# untitled.net
KiCad netlist of a schematic drawn in EAGLE
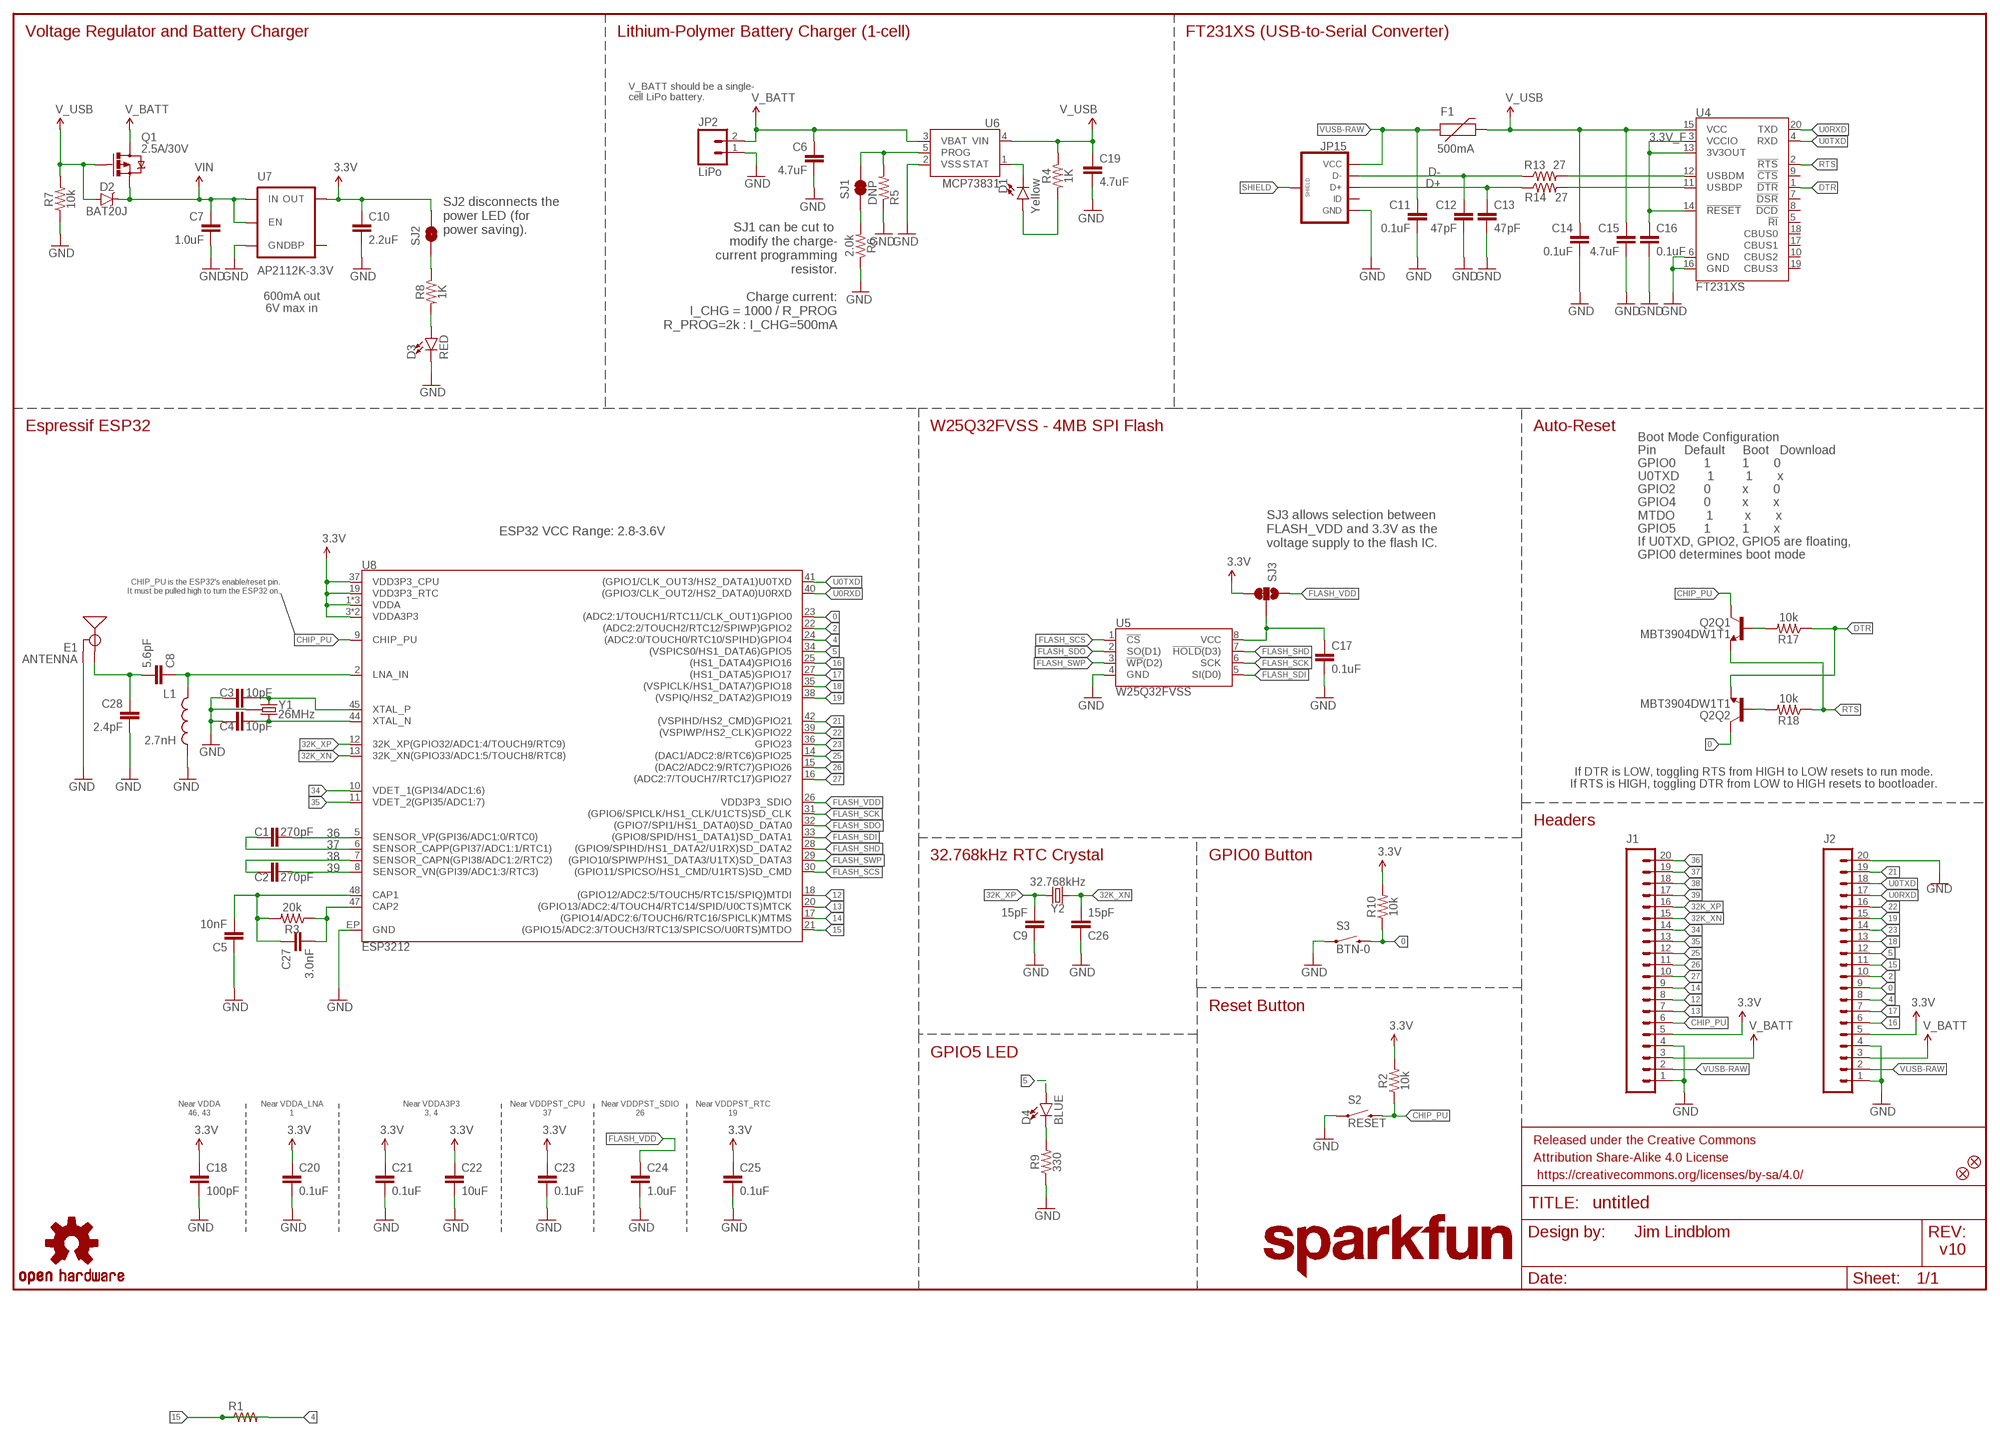
[diagram p0: schematic, sheet 1]

(export (version "E")
  (design (tool "Eeschema 10.0.6"))
  (components
    (comp (ref "C1")
      (value "270pF")
      (footprint "eagle-import:0603")
      (libsource (lib "eagle-import") (part "270PF-50V-5%(0603)"))
    )
    (comp (ref "C2")
      (value "270pF")
      (footprint "eagle-import:0603")
      (libsource (lib "eagle-import") (part "270PF-50V-5%(0603)"))
    )
    (comp (ref "C3")
      (value "10pF")
      (footprint "eagle-import:0603")
      (libsource (lib "eagle-import") (part "10PF-0603-50V-5%"))
    )
    (comp (ref "C4")
      (value "10pF")
      (footprint "eagle-import:0603")
      (libsource (lib "eagle-import") (part "10PF-0603-50V-5%"))
    )
    (comp (ref "C5")
      (value "10nF")
      (footprint "eagle-import:0603")
      (libsource (lib "eagle-import") (part "10NF-0603-50V-10%"))
    )
    (comp (ref "C6")
      (value "4.7uF")
      (footprint "eagle-import:0603")
      (libsource (lib "eagle-import") (part "4.7UF0603"))
    )
    (comp (ref "C7")
      (value "1.0uF")
      (footprint "eagle-import:0805")
      (libsource (lib "eagle-import") (part "1.0UF-0805-25V-(+80/-20%)"))
    )
    (comp (ref "C8")
      (value "5.6pF")
      (footprint "eagle-import:0603")
      (libsource (lib "eagle-import") (part "5.6PF-50V-5%(0603)"))
    )
    (comp (ref "C9")
      (value "15pF")
      (footprint "eagle-import:0603")
      (libsource (lib "eagle-import") (part "15PF-0603-50V-5%"))
    )
    (comp (ref "C10")
      (value "2.2uF")
      (footprint "eagle-import:0603")
      (libsource (lib "eagle-import") (part "2.2UF-0603-10V-20%"))
    )
    (comp (ref "C11")
      (value "0.1uF")
      (footprint "eagle-import:0603")
      (libsource (lib "eagle-import") (part "0.1UF-0603-25V-(+80/-20%)"))
    )
    (comp (ref "C12")
      (value "47pF")
      (footprint "eagle-import:0603")
      (libsource (lib "eagle-import") (part "47PF-0603-50V-5%"))
    )
    (comp (ref "C13")
      (value "47pF")
      (footprint "eagle-import:0603")
      (libsource (lib "eagle-import") (part "47PF-0603-50V-5%"))
    )
    (comp (ref "C14")
      (value "0.1uF")
      (footprint "eagle-import:0603")
      (libsource (lib "eagle-import") (part "0.1UF-0603-25V-(+80/-20%)"))
    )
    (comp (ref "C15")
      (value "4.7uF")
      (footprint "eagle-import:0603-CAP")
      (libsource (lib "eagle-import") (part "4.7UF-6.3V-10%(0603)0603"))
    )
    (comp (ref "C16")
      (value "0.1uF")
      (footprint "eagle-import:0603")
      (libsource (lib "eagle-import") (part "0.1UF-0603-25V-(+80/-20%)"))
    )
    (comp (ref "C17")
      (value "0.1uF")
      (footprint "eagle-import:0603")
      (libsource (lib "eagle-import") (part "0.1UF-0603-25V-(+80/-20%)"))
    )
    (comp (ref "C18")
      (value "100pF")
      (footprint "eagle-import:0603")
      (libsource (lib "eagle-import") (part "100PF-0603-50V-5%"))
    )
    (comp (ref "C19")
      (value "4.7uF")
      (footprint "eagle-import:0603")
      (libsource (lib "eagle-import") (part "4.7UF0603"))
    )
    (comp (ref "C20")
      (value "0.1uF")
      (footprint "eagle-import:0603")
      (libsource (lib "eagle-import") (part "0.1UF-0603-25V-(+80/-20%)"))
    )
    (comp (ref "C21")
      (value "0.1uF")
      (footprint "eagle-import:0603")
      (libsource (lib "eagle-import") (part "0.1UF-0603-25V-(+80/-20%)"))
    )
    (comp (ref "C22")
      (value "10uF")
      (footprint "eagle-import:0603")
      (libsource (lib "eagle-import") (part "10UF-0603-6.3V-20%"))
    )
    (comp (ref "C23")
      (value "0.1uF")
      (footprint "eagle-import:0603")
      (libsource (lib "eagle-import") (part "0.1UF-0603-25V-(+80/-20%)"))
    )
    (comp (ref "C24")
      (value "1.0uF")
      (footprint "eagle-import:0603")
      (libsource (lib "eagle-import") (part "1.0UF-0603-16V-10%"))
    )
    (comp (ref "C25")
      (value "0.1uF")
      (footprint "eagle-import:0603")
      (libsource (lib "eagle-import") (part "0.1UF-0603-25V-(+80/-20%)"))
    )
    (comp (ref "C26")
      (value "15pF")
      (footprint "eagle-import:0603")
      (libsource (lib "eagle-import") (part "15PF-0603-50V-5%"))
    )
    (comp (ref "C27")
      (value "3.0nF")
      (footprint "eagle-import:0603")
      (libsource (lib "eagle-import") (part "3.0NF-0603-50V-5%"))
    )
    (comp (ref "C28")
      (value "2.4pF")
      (footprint "eagle-import:0603")
      (libsource (lib "eagle-import") (part "2.4PF-0603-50V-5%"))
    )
    (comp (ref "D1")
      (value "Yellow")
      (footprint "eagle-import:LED-0603")
      (libsource (lib "eagle-import") (part "LED-YELLOW0603"))
    )
    (comp (ref "D2")
      (value "BAT20J")
      (footprint "eagle-import:SOD-323")
      (libsource (lib "eagle-import") (part "DIODE-SCHOTTKY-BAT20J"))
    )
    (comp (ref "D3")
      (value "RED")
      (footprint "eagle-import:LED-0603")
      (libsource (lib "eagle-import") (part "LED-RED0603"))
    )
    (comp (ref "D4")
      (value "BLUE")
      (footprint "eagle-import:LED-0603")
      (libsource (lib "eagle-import") (part "LED-BLUE0603"))
    )
    (comp (ref "E1")
      (value "ANTENNA")
      (footprint "eagle-import:TRACE_ANTENNA_2.4GHZ_25.7MM_TUNED")
      (libsource (lib "eagle-import") (part "ANTENNATRACE-TUNED"))
    )
    (comp (ref "F1")
      (value "500mA")
      (footprint "eagle-import:PTC-1206")
      (libsource (lib "eagle-import") (part "PTCSMD"))
    )
    (comp (ref "FD1")
      (value "FIDUCIALUFIDUCIAL")
      (footprint "eagle-import:MICRO-FIDUCIAL")
      (libsource (lib "eagle-import") (part "FIDUCIALUFIDUCIAL"))
    )
    (comp (ref "FD2")
      (value "FIDUCIALUFIDUCIAL")
      (footprint "eagle-import:MICRO-FIDUCIAL")
      (libsource (lib "eagle-import") (part "FIDUCIALUFIDUCIAL"))
    )
    (comp (ref "FRAME2")
      (value "FRAME-LEDGER")
      (footprint "eagle-import:CREATIVE_COMMONS")
      (libsource (lib "eagle-import") (part "FRAME-LEDGER"))
    )
    (comp (ref "J1")
      (value "M20NOSILK")
      (footprint "eagle-import:1X20_NOSILK")
      (libsource (lib "eagle-import") (part "M20NOSILK"))
    )
    (comp (ref "J2")
      (value "M20NOSILK")
      (footprint "eagle-import:1X20_NOSILK")
      (libsource (lib "eagle-import") (part "M20NOSILK"))
    )
    (comp (ref "JP2")
      (value "LiPo")
      (footprint "eagle-import:JST-2-PTH")
      (libsource (lib "eagle-import") (part "M02JST-PTH-2"))
    )
    (comp (ref "JP15")
      (value "USB_MICROB_PLUGCONN-11752")
      (footprint "eagle-import:USB-B-MICRO-SMD_V03")
      (libsource (lib "eagle-import") (part "USB_MICROB_PLUGCONN-11752"))
    )
    (comp (ref "L1")
      (value "2.7nH")
      (footprint "eagle-import:0603")
      (libsource (lib "eagle-import") (part "INDUCTOR0603"))
    )
    (comp (ref "LOGO1")
      (value "SFE_LOGO_NAME.2_INCH")
      (footprint "eagle-import:SFE_LOGO_NAME_.2")
      (libsource (lib "eagle-import") (part "SFE_LOGO_NAME.2_INCH"))
    )
    (comp (ref "LOGO2")
      (value "OSHW-LOGOMINI")
      (footprint "eagle-import:OSHW-LOGO-MINI")
      (libsource (lib "eagle-import") (part "OSHW-LOGOMINI"))
    )
    (comp (ref "LOGO3")
      (value "SFE_LOGO_NAME.2_INCH")
      (footprint "eagle-import:SFE_LOGO_NAME_.2")
      (libsource (lib "eagle-import") (part "SFE_LOGO_NAME.2_INCH"))
    )
    (comp (ref "Q1")
      (value "2.5A/30V")
      (footprint "eagle-import:SOT23-3")
      (libsource (lib "eagle-import") (part "MOSFET-PCHANNELDMG2307L"))
    )
    (comp (ref "Q2")
      (value "MBT3904DW1T1")
      (footprint "eagle-import:SC70-6")
      (libsource (lib "eagle-import") (part "MBT3904DW1T1"))
    )
    (comp (ref "R1")
      (value "R-US_M0805")
      (footprint "eagle-import:M0805")
      (libsource (lib "eagle-import") (part "R-US_M0805"))
    )
    (comp (ref "R2")
      (value "10k")
      (footprint "eagle-import:0603")
      (libsource (lib "eagle-import") (part "10KOHM-1/10W-1%(0603)0603"))
    )
    (comp (ref "R3")
      (value "20k")
      (footprint "eagle-import:0603")
      (libsource (lib "eagle-import") (part "20KOHM-0603-1/10W-1%"))
    )
    (comp (ref "R4")
      (value "1K")
      (footprint "eagle-import:0603")
      (libsource (lib "eagle-import") (part "1KOHM-1/10W-1%(0603)"))
    )
    (comp (ref "R5")
      (value "DNP")
      (footprint "eagle-import:1_6W-RES")
      (libsource (lib "eagle-import") (part "RESISTORPTH-1/6W"))
    )
    (comp (ref "R6")
      (value "2.0k")
      (footprint "eagle-import:0603")
      (libsource (lib "eagle-import") (part "2.0KOHM1/10W5%(0603)"))
    )
    (comp (ref "R7")
      (value "10k")
      (footprint "eagle-import:0603")
      (libsource (lib "eagle-import") (part "10KOHM-0603-1/10W-1%"))
    )
    (comp (ref "R8")
      (value "1K")
      (footprint "eagle-import:0603")
      (libsource (lib "eagle-import") (part "1KOHM-1/10W-1%(0603)"))
    )
    (comp (ref "R9")
      (value "330")
      (footprint "eagle-import:0603")
      (libsource (lib "eagle-import") (part "330OHM1/10W1%(0603)"))
    )
    (comp (ref "R10")
      (value "10k")
      (footprint "eagle-import:0603")
      (libsource (lib "eagle-import") (part "10KOHM-1/10W-1%(0603)0603"))
    )
    (comp (ref "R13")
      (value "27")
      (footprint "eagle-import:0603")
      (libsource (lib "eagle-import") (part "27OHM1/10W1%(0603)0603-RES"))
    )
    (comp (ref "R14")
      (value "27")
      (footprint "eagle-import:0603")
      (libsource (lib "eagle-import") (part "27OHM1/10W1%(0603)0603-RES"))
    )
    (comp (ref "R17")
      (value "10k")
      (footprint "eagle-import:0603")
      (libsource (lib "eagle-import") (part "10KOHM-0603-1/10W-1%"))
    )
    (comp (ref "R18")
      (value "10k")
      (footprint "eagle-import:0603")
      (libsource (lib "eagle-import") (part "10KOHM-0603-1/10W-1%"))
    )
    (comp (ref "S2")
      (value "RESET")
      (footprint "eagle-import:TACTILE_SWITCH_SMD_4.6X2.8MM")
      (libsource (lib "eagle-import") (part "SWITCH-MOMENTARY-2SMD-4.6X2.8MM"))
    )
    (comp (ref "S3")
      (value "BTN-0")
      (footprint "eagle-import:TACTILE_SWITCH_SMD_4.6X2.8MM")
      (libsource (lib "eagle-import") (part "SWITCH-MOMENTARY-2SMD-4.6X2.8MM"))
    )
    (comp (ref "SJ1")
      (value "JUMPER-PAD-2-NC_BY_TRACE")
      (footprint "eagle-import:PAD-JUMPER-2-NC_BY_TRACE_YES_SILK")
      (libsource (lib "eagle-import") (part "JUMPER-PAD-2-NC_BY_TRACE"))
    )
    (comp (ref "SJ2")
      (value "JUMPER-PAD-2-NC_BY_TRACE")
      (footprint "eagle-import:PAD-JUMPER-2-NC_BY_TRACE_YES_SILK")
      (libsource (lib "eagle-import") (part "JUMPER-PAD-2-NC_BY_TRACE"))
    )
    (comp (ref "SJ3")
      (value "JUMPER-PAD-3-2OF3_NC_BY_TRACE_SMALL")
      (footprint "eagle-import:PAD-JUMPER-3-2OF3_NC_BY_TRACE_YES_SILK_FULL_BOX")
      (libsource (lib "eagle-import") (part "JUMPER-PAD-3-2OF3_NC_BY_TRACE_SMALL"))
    )
    (comp (ref "U4")
      (value "FT231XS")
      (footprint "eagle-import:SSOP20_L")
      (libsource (lib "eagle-import") (part "FT231XS"))
    )
    (comp (ref "U5")
      (value "W25Q32FVSS")
      (footprint "eagle-import:SOIC-8")
      (libsource (lib "eagle-import") (part "W25Q32FVSS"))
    )
    (comp (ref "U6")
      (value "MCP73831")
      (footprint "eagle-import:SOT23-5")
      (libsource (lib "eagle-import") (part "MCP73831"))
    )
    (comp (ref "U7")
      (value "AP2112K-3.3V")
      (footprint "eagle-import:SOT23-5")
      (libsource (lib "eagle-import") (part "V_REG_LDOSMD"))
    )
    (comp (ref "U8")
      (value "ESP3212")
      (footprint "eagle-import:QFN48-0.4MM")
      (libsource (lib "eagle-import") (part "ESP3212"))
    )
    (comp (ref "Y1")
      (value "26MHz")
      (footprint "eagle-import:CRYSTAL-SMD-3.2X2.5")
      (libsource (lib "eagle-import") (part "CRYSTAL-GROUNDED3.2X2.5"))
    )
    (comp (ref "Y2")
      (value "32.768kHz")
      (footprint "eagle-import:CRYSTAL-SMD-3.2X1.5MM")
      (libsource (lib "eagle-import") (part "CRYSTAL-32.768KHZSMD-3.2X1.5"))
    )
  )
  (nets
    (net (code "1") (name "/3.3V_F") (class "Default")
      (node (ref "C16") (pin "1") (pinfunction "1_1") (pintype "passive"))
      (node (ref "U4") (pin "13") (pinfunction "3V3OUT_13") (pintype "bidirectional"))
      (node (ref "U4") (pin "14") (pinfunction "~{RESET}_14") (pintype "bidirectional"))
      (node (ref "U4") (pin "3") (pinfunction "VCCIO_3") (pintype "bidirectional"))
    )
    (net (code "2") (name "/D+") (class "Default")
      (node (ref "C13") (pin "1") (pinfunction "1_1") (pintype "passive"))
      (node (ref "JP15") (pin "D+") (pinfunction "D+_D+") (pintype "bidirectional"))
      (node (ref "R14") (pin "1") (pinfunction "1_1") (pintype "passive"))
    )
    (net (code "3") (name "/D-") (class "Default")
      (node (ref "C12") (pin "1") (pinfunction "1_1") (pintype "passive"))
      (node (ref "JP15") (pin "D-") (pinfunction "D-_D-") (pintype "bidirectional"))
      (node (ref "R13") (pin "1") (pinfunction "1_1") (pintype "passive"))
    )
    (net (code "4") (name "0") (class "Default")
      (node (ref "J2") (pin "9") (pinfunction "9_9") (pintype "passive"))
      (node (ref "Q2") (pin "6") (pinfunction "C_6") (pintype "passive"))
      (node (ref "R10") (pin "1") (pinfunction "1_1") (pintype "passive"))
      (node (ref "S3") (pin "3") (pinfunction "2_3") (pintype "passive"))
      (node (ref "S3") (pin "4") (pinfunction "2_4") (pintype "passive"))
      (node (ref "U8") (pin "23") (pinfunction "(ADC2:1/TOUCH1/RTC11/CLK_OUT1)GPIO0_23") (pintype "bidirectional"))
    )
    (net (code "5") (name "2") (class "Default")
      (node (ref "J2") (pin "10") (pinfunction "10_10") (pintype "passive"))
      (node (ref "U8") (pin "22") (pinfunction "(ADC2:2/TOUCH2/RTC12/SPIWP)GPIO2_22") (pintype "bidirectional"))
    )
    (net (code "6") (name "3.3V") (class "Default")
      (node (ref "C10") (pin "1") (pinfunction "1_1") (pintype "passive"))
      (node (ref "C18") (pin "1") (pinfunction "1_1") (pintype "passive"))
      (node (ref "C20") (pin "1") (pinfunction "1_1") (pintype "passive"))
      (node (ref "C21") (pin "1") (pinfunction "1_1") (pintype "passive"))
      (node (ref "C22") (pin "1") (pinfunction "1_1") (pintype "passive"))
      (node (ref "C23") (pin "1") (pinfunction "1_1") (pintype "passive"))
      (node (ref "C25") (pin "1") (pinfunction "1_1") (pintype "passive"))
      (node (ref "J1") (pin "5") (pinfunction "5_5") (pintype "passive"))
      (node (ref "J2") (pin "5") (pinfunction "5_5") (pintype "passive"))
      (node (ref "R10") (pin "2") (pinfunction "2_2") (pintype "passive"))
      (node (ref "R2") (pin "2") (pinfunction "2_2") (pintype "passive"))
      (node (ref "SJ2") (pin "2") (pinfunction "2_2") (pintype "passive"))
      (node (ref "SJ3") (pin "3") (pinfunction "3_3") (pintype "passive"))
      (node (ref "U7") (pin "5") (pinfunction "OUT_5") (pintype "passive"))
      (node (ref "U8") (pin "1") (pinfunction "VDDA_1") (pintype "bidirectional"))
      (node (ref "U8") (pin "19") (pinfunction "VDD3P3_RTC_19") (pintype "bidirectional"))
      (node (ref "U8") (pin "3") (pinfunction "VDDA3P3_3") (pintype "bidirectional"))
      (node (ref "U8") (pin "37") (pinfunction "VDD3P3_CPU_37") (pintype "bidirectional"))
      (node (ref "U8") (pin "4") (pinfunction "VDDA3P3_4") (pintype "bidirectional"))
      (node (ref "U8") (pin "43") (pinfunction "VDDA_43") (pintype "bidirectional"))
      (node (ref "U8") (pin "46") (pinfunction "VDDA_46") (pintype "bidirectional"))
    )
    (net (code "7") (name "4") (class "Default")
      (node (ref "J2") (pin "8") (pinfunction "8_8") (pintype "passive"))
      (node (ref "U8") (pin "24") (pinfunction "(ADC2:0/TOUCH0/RTC10/SPIHD)GPIO4_24") (pintype "bidirectional"))
    )
    (net (code "8") (name "5") (class "Default")
      (node (ref "D4") (pin "A") (pinfunction "A_A") (pintype "passive"))
      (node (ref "J2") (pin "12") (pinfunction "12_12") (pintype "passive"))
      (node (ref "U8") (pin "34") (pinfunction "(VSPICS0/HS1_DATA6)GPIO5_34") (pintype "bidirectional"))
    )
    (net (code "9") (name "12") (class "Default")
      (node (ref "J1") (pin "8") (pinfunction "8_8") (pintype "passive"))
      (node (ref "U8") (pin "18") (pinfunction "(GPIO12/ADC2:5/TOUCH5/RTC15/SPIQ)MTDI_18") (pintype "bidirectional"))
    )
    (net (code "10") (name "13") (class "Default")
      (node (ref "J1") (pin "7") (pinfunction "7_7") (pintype "passive"))
      (node (ref "U8") (pin "20") (pinfunction "(GPIO13/ADC2:4/TOUCH4/RTC14/SPID/U0CTS)MTCK_20") (pintype "bidirectional"))
    )
    (net (code "11") (name "14") (class "Default")
      (node (ref "J1") (pin "9") (pinfunction "9_9") (pintype "passive"))
      (node (ref "U8") (pin "17") (pinfunction "(GPIO14/ADC2:6/TOUCH6/RTC16/SPICLK)MTMS_17") (pintype "bidirectional"))
    )
    (net (code "12") (name "15") (class "Default")
      (node (ref "J2") (pin "11") (pinfunction "11_11") (pintype "passive"))
      (node (ref "U8") (pin "21") (pinfunction "(GPIO15/ADC2:3/TOUCH3/RTC13/SPICSO/U0RTS)MTDO_21") (pintype "bidirectional"))
    )
    (net (code "13") (name "16") (class "Default")
      (node (ref "J2") (pin "6") (pinfunction "6_6") (pintype "passive"))
      (node (ref "U8") (pin "25") (pinfunction "(HS1_DATA4)GPIO16_25") (pintype "bidirectional"))
    )
    (net (code "14") (name "17") (class "Default")
      (node (ref "J2") (pin "7") (pinfunction "7_7") (pintype "passive"))
      (node (ref "U8") (pin "27") (pinfunction "(HS1_DATA5)GPIO17_27") (pintype "bidirectional"))
    )
    (net (code "15") (name "18") (class "Default")
      (node (ref "J2") (pin "13") (pinfunction "13_13") (pintype "passive"))
      (node (ref "U8") (pin "35") (pinfunction "(VSPICLK/HS1_DATA7)GPIO18_35") (pintype "bidirectional"))
    )
    (net (code "16") (name "19") (class "Default")
      (node (ref "J2") (pin "15") (pinfunction "15_15") (pintype "passive"))
      (node (ref "U8") (pin "38") (pinfunction "(VSPIQ/HS2_DATA2)GPIO19_38") (pintype "bidirectional"))
    )
    (net (code "17") (name "21") (class "Default")
      (node (ref "J2") (pin "19") (pinfunction "19_19") (pintype "passive"))
      (node (ref "U8") (pin "42") (pinfunction "(VSPIHD/HS2_CMD)GPIO21_42") (pintype "bidirectional"))
    )
    (net (code "18") (name "22") (class "Default")
      (node (ref "J2") (pin "16") (pinfunction "16_16") (pintype "passive"))
      (node (ref "U8") (pin "39") (pinfunction "(VSPIWP/HS2_CLK)GPIO22_39") (pintype "bidirectional"))
    )
    (net (code "19") (name "23") (class "Default")
      (node (ref "J2") (pin "14") (pinfunction "14_14") (pintype "passive"))
      (node (ref "U8") (pin "36") (pinfunction "GPIO23_36") (pintype "bidirectional"))
    )
    (net (code "20") (name "25") (class "Default")
      (node (ref "J1") (pin "12") (pinfunction "12_12") (pintype "passive"))
      (node (ref "U8") (pin "14") (pinfunction "(DAC1/ADC2:8/RTC6)GPIO25_14") (pintype "bidirectional"))
    )
    (net (code "21") (name "26") (class "Default")
      (node (ref "J1") (pin "11") (pinfunction "11_11") (pintype "passive"))
      (node (ref "U8") (pin "15") (pinfunction "(DAC2/ADC2:9/RTC7)GPIO26_15") (pintype "bidirectional"))
    )
    (net (code "22") (name "27") (class "Default")
      (node (ref "J1") (pin "10") (pinfunction "10_10") (pintype "passive"))
      (node (ref "U8") (pin "16") (pinfunction "(ADC2:7/TOUCH7/RTC17)GPIO27_16") (pintype "bidirectional"))
    )
    (net (code "23") (name "32K_XN") (class "Default")
      (node (ref "C26") (pin "2") (pinfunction "2_2") (pintype "passive"))
      (node (ref "J1") (pin "15") (pinfunction "15_15") (pintype "passive"))
      (node (ref "U8") (pin "13") (pinfunction "32K_XN(GPIO33/ADC1:5/TOUCH8/RTC8)_13") (pintype "bidirectional"))
      (node (ref "Y2") (pin "P$2") (pinfunction "2_P$2") (pintype "passive"))
    )
    (net (code "24") (name "32K_XP") (class "Default")
      (node (ref "C9") (pin "2") (pinfunction "2_2") (pintype "passive"))
      (node (ref "J1") (pin "16") (pinfunction "16_16") (pintype "passive"))
      (node (ref "U8") (pin "12") (pinfunction "32K_XP(GPIO32/ADC1:4/TOUCH9/RTC9)_12") (pintype "bidirectional"))
      (node (ref "Y2") (pin "P$1") (pinfunction "1_P$1") (pintype "passive"))
    )
    (net (code "25") (name "34") (class "Default")
      (node (ref "J1") (pin "14") (pinfunction "14_14") (pintype "passive"))
      (node (ref "U8") (pin "10") (pinfunction "VDET_1(GPI34/ADC1:6)_10") (pintype "bidirectional"))
    )
    (net (code "26") (name "35") (class "Default")
      (node (ref "J1") (pin "13") (pinfunction "13_13") (pintype "passive"))
      (node (ref "U8") (pin "11") (pinfunction "VDET_2(GPI35/ADC1:7)_11") (pintype "bidirectional"))
    )
    (net (code "27") (name "36") (class "Default")
      (node (ref "C1") (pin "2") (pinfunction "2_2") (pintype "passive"))
      (node (ref "J1") (pin "20") (pinfunction "20_20") (pintype "passive"))
      (node (ref "U8") (pin "5") (pinfunction "SENSOR_VP(GPI36/ADC1:0/RTC0)_5") (pintype "bidirectional"))
    )
    (net (code "28") (name "37") (class "Default")
      (node (ref "C1") (pin "1") (pinfunction "1_1") (pintype "passive"))
      (node (ref "J1") (pin "19") (pinfunction "19_19") (pintype "passive"))
      (node (ref "U8") (pin "6") (pinfunction "SENSOR_CAPP(GPI37/ADC1:1/RTC1)_6") (pintype "bidirectional"))
    )
    (net (code "29") (name "38") (class "Default")
      (node (ref "C2") (pin "1") (pinfunction "1_1") (pintype "passive"))
      (node (ref "J1") (pin "18") (pinfunction "18_18") (pintype "passive"))
      (node (ref "U8") (pin "7") (pinfunction "SENSOR_CAPN(GPI38/ADC1:2/RTC2)_7") (pintype "bidirectional"))
    )
    (net (code "30") (name "39") (class "Default")
      (node (ref "C2") (pin "2") (pinfunction "2_2") (pintype "passive"))
      (node (ref "J1") (pin "17") (pinfunction "17_17") (pintype "passive"))
      (node (ref "U8") (pin "8") (pinfunction "SENSOR_VN(GPI39/ADC1:3/RTC3)_8") (pintype "bidirectional"))
    )
    (net (code "31") (name "CHIP_PU") (class "Default")
      (node (ref "J1") (pin "6") (pinfunction "6_6") (pintype "passive"))
      (node (ref "Q2") (pin "3") (pinfunction "C_3") (pintype "passive"))
      (node (ref "R2") (pin "1") (pinfunction "1_1") (pintype "passive"))
      (node (ref "S2") (pin "3") (pinfunction "2_3") (pintype "passive"))
      (node (ref "S2") (pin "4") (pinfunction "2_4") (pintype "passive"))
      (node (ref "U8") (pin "9") (pinfunction "CHIP_PU_9") (pintype "bidirectional"))
    )
    (net (code "32") (name "DTR") (class "Default")
      (node (ref "Q2") (pin "1") (pinfunction "E_1") (pintype "passive"))
      (node (ref "R17") (pin "1") (pinfunction "1_1") (pintype "passive"))
      (node (ref "U4") (pin "1") (pinfunction "~{DTR}_1") (pintype "bidirectional"))
    )
    (net (code "33") (name "FLASH_SCK") (class "Default")
      (node (ref "U5") (pin "6") (pinfunction "SCK_6") (pintype "bidirectional"))
      (node (ref "U8") (pin "31") (pinfunction "(GPIO6/SPICLK/HS1_CLK/U1CTS)SD_CLK_31") (pintype "bidirectional"))
    )
    (net (code "34") (name "FLASH_SCS") (class "Default")
      (node (ref "U5") (pin "1") (pinfunction "~{CS}_1") (pintype "bidirectional"))
      (node (ref "U8") (pin "30") (pinfunction "(GPIO11/SPICSO/HS1_CMD/U1RTS)SD_CMD_30") (pintype "bidirectional"))
    )
    (net (code "35") (name "FLASH_SDI") (class "Default")
      (node (ref "U5") (pin "5") (pinfunction "SI(D0)_5") (pintype "bidirectional"))
      (node (ref "U8") (pin "33") (pinfunction "(GPIO8/SPID/HS1_DATA1)SD_DATA1_33") (pintype "bidirectional"))
    )
    (net (code "36") (name "FLASH_SDO") (class "Default")
      (node (ref "U5") (pin "2") (pinfunction "SO(D1)_2") (pintype "bidirectional"))
      (node (ref "U8") (pin "32") (pinfunction "(GPIO7/SPI1/HS1_DATA0)SD_DATA0_32") (pintype "bidirectional"))
    )
    (net (code "37") (name "FLASH_SHD") (class "Default")
      (node (ref "U5") (pin "7") (pinfunction "~{HOLD}(D3)_7") (pintype "bidirectional"))
      (node (ref "U8") (pin "28") (pinfunction "(GPIO9/SPIHD/HS1_DATA2/U1RX)SD_DATA2_28") (pintype "bidirectional"))
    )
    (net (code "38") (name "FLASH_SWP") (class "Default")
      (node (ref "U5") (pin "3") (pinfunction "~{WP}(D2)_3") (pintype "bidirectional"))
      (node (ref "U8") (pin "29") (pinfunction "(GPIO10/SPIWP/HS1_DATA3/U1TX)SD_DATA3_29") (pintype "bidirectional"))
    )
    (net (code "39") (name "FLASH_VDD") (class "Default")
      (node (ref "C24") (pin "1") (pinfunction "1_1") (pintype "passive"))
      (node (ref "SJ3") (pin "1") (pinfunction "1_1") (pintype "passive"))
      (node (ref "U8") (pin "26") (pinfunction "VDD3P3_SDIO_26") (pintype "bidirectional"))
    )
    (net (code "40") (name "GND") (class "Default")
      (node (ref "C10") (pin "2") (pinfunction "2_2") (pintype "passive"))
      (node (ref "C11") (pin "2") (pinfunction "2_2") (pintype "passive"))
      (node (ref "C12") (pin "2") (pinfunction "2_2") (pintype "passive"))
      (node (ref "C13") (pin "2") (pinfunction "2_2") (pintype "passive"))
      (node (ref "C14") (pin "2") (pinfunction "2_2") (pintype "passive"))
      (node (ref "C15") (pin "2") (pinfunction "2_2") (pintype "passive"))
      (node (ref "C16") (pin "2") (pinfunction "2_2") (pintype "passive"))
      (node (ref "C17") (pin "2") (pinfunction "2_2") (pintype "passive"))
      (node (ref "C18") (pin "2") (pinfunction "2_2") (pintype "passive"))
      (node (ref "C19") (pin "2") (pinfunction "2_2") (pintype "passive"))
      (node (ref "C20") (pin "2") (pinfunction "2_2") (pintype "passive"))
      (node (ref "C21") (pin "2") (pinfunction "2_2") (pintype "passive"))
      (node (ref "C22") (pin "2") (pinfunction "2_2") (pintype "passive"))
      (node (ref "C23") (pin "2") (pinfunction "2_2") (pintype "passive"))
      (node (ref "C24") (pin "2") (pinfunction "2_2") (pintype "passive"))
      (node (ref "C25") (pin "2") (pinfunction "2_2") (pintype "passive"))
      (node (ref "C26") (pin "1") (pinfunction "1_1") (pintype "passive"))
      (node (ref "C28") (pin "2") (pinfunction "2_2") (pintype "passive"))
      (node (ref "C3") (pin "1") (pinfunction "1_1") (pintype "passive"))
      (node (ref "C4") (pin "1") (pinfunction "1_1") (pintype "passive"))
      (node (ref "C5") (pin "1") (pinfunction "1_1") (pintype "passive"))
      (node (ref "C6") (pin "2") (pinfunction "2_2") (pintype "passive"))
      (node (ref "C7") (pin "2") (pinfunction "2_2") (pintype "passive"))
      (node (ref "C9") (pin "1") (pinfunction "1_1") (pintype "passive"))
      (node (ref "D3") (pin "C") (pinfunction "C_C") (pintype "passive"))
      (node (ref "E1") (pin "GND") (pinfunction "GND_GND") (pintype "bidirectional"))
      (node (ref "E1") (pin "GND2") (pinfunction "GND_GND2") (pintype "bidirectional"))
      (node (ref "J1") (pin "1") (pinfunction "1_1") (pintype "passive"))
      (node (ref "J1") (pin "4") (pinfunction "4_4") (pintype "passive"))
      (node (ref "J2") (pin "1") (pinfunction "1_1") (pintype "passive"))
      (node (ref "J2") (pin "20") (pinfunction "20_20") (pintype "passive"))
      (node (ref "J2") (pin "4") (pinfunction "4_4") (pintype "passive"))
      (node (ref "JP15") (pin "GND") (pinfunction "GND_GND") (pintype "bidirectional"))
      (node (ref "JP2") (pin "1") (pinfunction "1_1") (pintype "passive"))
      (node (ref "L1") (pin "2") (pinfunction "2_2") (pintype "passive"))
      (node (ref "R5") (pin "1") (pinfunction "1_1") (pintype "passive"))
      (node (ref "R6") (pin "1") (pinfunction "1_1") (pintype "passive"))
      (node (ref "R7") (pin "1") (pinfunction "1_1") (pintype "passive"))
      (node (ref "R9") (pin "1") (pinfunction "1_1") (pintype "passive"))
      (node (ref "S2") (pin "1") (pinfunction "1_1") (pintype "passive"))
      (node (ref "S2") (pin "2") (pinfunction "1_2") (pintype "passive"))
      (node (ref "S3") (pin "1") (pinfunction "1_1") (pintype "passive"))
      (node (ref "S3") (pin "2") (pinfunction "1_2") (pintype "passive"))
      (node (ref "U4") (pin "16") (pinfunction "GND_16") (pintype "bidirectional"))
      (node (ref "U4") (pin "6") (pinfunction "GND_6") (pintype "bidirectional"))
      (node (ref "U5") (pin "4") (pinfunction "GND_4") (pintype "bidirectional"))
      (node (ref "U6") (pin "2") (pinfunction "VSS_2") (pintype "power_in"))
      (node (ref "U7") (pin "2") (pinfunction "GND_2") (pintype "input"))
      (node (ref "U8") (pin "EP") (pinfunction "GND_EP") (pintype "bidirectional"))
      (node (ref "Y1") (pin "2") (pinfunction "GND_2") (pintype "passive"))
      (node (ref "Y1") (pin "4") (pinfunction "GND_4") (pintype "passive"))
    )
    (net (code "41") (name "Net-(D1-PadA)") (class "Default")
      (node (ref "D1") (pin "A") (pinfunction "A_A") (pintype "passive"))
      (node (ref "R4") (pin "2") (pinfunction "2_2") (pintype "passive"))
    )
    (net (code "42") (name "Net-(D3-PadA)") (class "Default")
      (node (ref "D3") (pin "A") (pinfunction "A_A") (pintype "passive"))
      (node (ref "R8") (pin "2") (pinfunction "2_2") (pintype "passive"))
    )
    (net (code "43") (name "Net-(D4-PadC)") (class "Default")
      (node (ref "D4") (pin "C") (pinfunction "C_C") (pintype "passive"))
      (node (ref "R9") (pin "2") (pinfunction "2_2") (pintype "passive"))
    )
    (net (code "44") (name "Net-(E1-SIGNAL)") (class "Default")
      (node (ref "C28") (pin "1") (pinfunction "1_1") (pintype "passive"))
      (node (ref "C8") (pin "2") (pinfunction "2_2") (pintype "passive"))
      (node (ref "E1") (pin "ANT") (pinfunction "SIGNAL_ANT") (pintype "bidirectional"))
    )
    (net (code "45") (name "Net-(Q2A-B)") (class "Default")
      (node (ref "Q2") (pin "5") (pinfunction "B_5") (pintype "passive"))
      (node (ref "R17") (pin "2") (pinfunction "2_2") (pintype "passive"))
    )
    (net (code "46") (name "Net-(Q2B-B)") (class "Default")
      (node (ref "Q2") (pin "2") (pinfunction "B_2") (pintype "passive"))
      (node (ref "R18") (pin "2") (pinfunction "2_2") (pintype "passive"))
    )
    (net (code "47") (name "Net-(R1-Pad1)") (class "Default")
      (node (ref "R1") (pin "1") (pinfunction "1_1") (pintype "passive"))
      (node (ref "R1") (pin "2") (pinfunction "2_2") (pintype "passive"))
    )
    (net (code "48") (name "Net-(R6-Pad2)") (class "Default")
      (node (ref "R6") (pin "2") (pinfunction "2_2") (pintype "passive"))
      (node (ref "SJ1") (pin "1") (pinfunction "1_1") (pintype "passive"))
    )
    (net (code "49") (name "Net-(R8-Pad1)") (class "Default")
      (node (ref "R8") (pin "1") (pinfunction "1_1") (pintype "passive"))
      (node (ref "SJ2") (pin "1") (pinfunction "1_1") (pintype "passive"))
    )
    (net (code "50") (name "Net-(U4-USBDM)") (class "Default")
      (node (ref "R13") (pin "2") (pinfunction "2_2") (pintype "passive"))
      (node (ref "U4") (pin "12") (pinfunction "USBDM_12") (pintype "bidirectional"))
    )
    (net (code "51") (name "Net-(U4-USBDP)") (class "Default")
      (node (ref "R14") (pin "2") (pinfunction "2_2") (pintype "passive"))
      (node (ref "U4") (pin "11") (pinfunction "USBDP_11") (pintype "bidirectional"))
    )
    (net (code "52") (name "Net-(U5-VCC)") (class "Default")
      (node (ref "C17") (pin "1") (pinfunction "1_1") (pintype "passive"))
      (node (ref "SJ3") (pin "2") (pinfunction "2_2") (pintype "passive"))
      (node (ref "U5") (pin "8") (pinfunction "VCC_8") (pintype "bidirectional"))
    )
    (net (code "53") (name "Net-(U6-PROG)") (class "Default")
      (node (ref "R5") (pin "2") (pinfunction "2_2") (pintype "passive"))
      (node (ref "SJ1") (pin "2") (pinfunction "2_2") (pintype "passive"))
      (node (ref "U6") (pin "5") (pinfunction "PROG_5") (pintype "input"))
    )
    (net (code "54") (name "Net-(U6-STAT)") (class "Default")
      (node (ref "D1") (pin "C") (pinfunction "C_C") (pintype "passive"))
      (node (ref "U6") (pin "1") (pinfunction "STAT_1") (pintype "output"))
    )
    (net (code "55") (name "Net-(U8-CAP1)") (class "Default")
      (node (ref "C27") (pin "1") (pinfunction "1_1") (pintype "passive"))
      (node (ref "C5") (pin "2") (pinfunction "2_2") (pintype "passive"))
      (node (ref "R3") (pin "2") (pinfunction "2_2") (pintype "passive"))
      (node (ref "U8") (pin "48") (pinfunction "CAP1_48") (pintype "bidirectional"))
    )
    (net (code "56") (name "Net-(U8-CAP2)") (class "Default")
      (node (ref "C27") (pin "2") (pinfunction "2_2") (pintype "passive"))
      (node (ref "R3") (pin "1") (pinfunction "1_1") (pintype "passive"))
      (node (ref "U8") (pin "47") (pinfunction "CAP2_47") (pintype "bidirectional"))
    )
    (net (code "57") (name "Net-(U8-LNA_IN)") (class "Default")
      (node (ref "C8") (pin "1") (pinfunction "1_1") (pintype "passive"))
      (node (ref "L1") (pin "1") (pinfunction "1_1") (pintype "passive"))
      (node (ref "U8") (pin "2") (pinfunction "LNA_IN_2") (pintype "bidirectional"))
    )
    (net (code "58") (name "Net-(U8-XTAL_N)") (class "Default")
      (node (ref "C4") (pin "2") (pinfunction "2_2") (pintype "passive"))
      (node (ref "U8") (pin "44") (pinfunction "XTAL_N_44") (pintype "bidirectional"))
      (node (ref "Y1") (pin "3") (pinfunction "2_3") (pintype "passive"))
    )
    (net (code "59") (name "Net-(U8-XTAL_P)") (class "Default")
      (node (ref "C3") (pin "2") (pinfunction "2_2") (pintype "passive"))
      (node (ref "U8") (pin "45") (pinfunction "XTAL_P_45") (pintype "bidirectional"))
      (node (ref "Y1") (pin "1") (pinfunction "1_1") (pintype "passive"))
    )
    (net (code "60") (name "RTS") (class "Default")
      (node (ref "Q2") (pin "4") (pinfunction "E_4") (pintype "passive"))
      (node (ref "R18") (pin "1") (pinfunction "1_1") (pintype "passive"))
      (node (ref "U4") (pin "2") (pinfunction "~{RTS}_2") (pintype "bidirectional"))
    )
    (net (code "61") (name "SHIELD") (class "Default")
      (node (ref "JP15") (pin "SHIELD1") (pinfunction "SHIELD_SHIELD1") (pintype "bidirectional"))
      (node (ref "JP15") (pin "SHIELD2") (pinfunction "SHIELD_SHIELD2") (pintype "bidirectional"))
      (node (ref "JP15") (pin "SHIELD3") (pinfunction "SHIELD_SHIELD3") (pintype "bidirectional"))
    )
    (net (code "62") (name "U0RXD") (class "Default")
      (node (ref "J2") (pin "17") (pinfunction "17_17") (pintype "passive"))
      (node (ref "U4") (pin "20") (pinfunction "TXD_20") (pintype "bidirectional"))
      (node (ref "U8") (pin "40") (pinfunction "(GPIO3/CLK_OUT2/HS2_DATA0)U0RXD_40") (pintype "bidirectional"))
    )
    (net (code "63") (name "U0TXD") (class "Default")
      (node (ref "J2") (pin "18") (pinfunction "18_18") (pintype "passive"))
      (node (ref "U4") (pin "4") (pinfunction "RXD_4") (pintype "bidirectional"))
      (node (ref "U8") (pin "41") (pinfunction "(GPIO1/CLK_OUT3/HS2_DATA1)U0TXD_41") (pintype "bidirectional"))
    )
    (net (code "64") (name "VIN") (class "Default")
      (node (ref "C7") (pin "1") (pinfunction "1_1") (pintype "passive"))
      (node (ref "D2") (pin "C") (pinfunction "C_C") (pintype "passive"))
      (node (ref "Q1") (pin "2") (pinfunction "S_2") (pintype "passive"))
      (node (ref "U7") (pin "1") (pinfunction "IN_1") (pintype "input"))
      (node (ref "U7") (pin "3") (pinfunction "EN_3") (pintype "input"))
    )
    (net (code "65") (name "VUSB-RAW") (class "Default")
      (node (ref "C11") (pin "1") (pinfunction "1_1") (pintype "passive"))
      (node (ref "F1") (pin "1") (pinfunction "1_1") (pintype "bidirectional"))
      (node (ref "J1") (pin "2") (pinfunction "2_2") (pintype "passive"))
      (node (ref "J2") (pin "2") (pinfunction "2_2") (pintype "passive"))
      (node (ref "JP15") (pin "VBUS") (pinfunction "VCC_VBUS") (pintype "bidirectional"))
    )
    (net (code "66") (name "V_BATT") (class "Default")
      (node (ref "C6") (pin "1") (pinfunction "1_1") (pintype "passive"))
      (node (ref "J1") (pin "3") (pinfunction "3_3") (pintype "passive"))
      (node (ref "J2") (pin "3") (pinfunction "3_3") (pintype "passive"))
      (node (ref "JP2") (pin "2") (pinfunction "2_2") (pintype "passive"))
      (node (ref "Q1") (pin "3") (pinfunction "D_3") (pintype "passive"))
      (node (ref "U6") (pin "3") (pinfunction "VBAT_3") (pintype "power_in"))
    )
    (net (code "67") (name "V_USB") (class "Default")
      (node (ref "C14") (pin "1") (pinfunction "1_1") (pintype "passive"))
      (node (ref "C15") (pin "1") (pinfunction "1_1") (pintype "passive"))
      (node (ref "C19") (pin "1") (pinfunction "1_1") (pintype "passive"))
      (node (ref "D2") (pin "A") (pinfunction "A_A") (pintype "passive"))
      (node (ref "F1") (pin "2") (pinfunction "2_2") (pintype "bidirectional"))
      (node (ref "Q1") (pin "1") (pinfunction "G_1") (pintype "passive"))
      (node (ref "R4") (pin "1") (pinfunction "1_1") (pintype "passive"))
      (node (ref "R7") (pin "2") (pinfunction "2_2") (pintype "passive"))
      (node (ref "U4") (pin "15") (pinfunction "VCC_15") (pintype "bidirectional"))
      (node (ref "U6") (pin "4") (pinfunction "VIN_4") (pintype "power_in"))
    )
    (net (code "68") (name "unconnected-(JP15-PadID)") (class "Default")
      (node (ref "JP15") (pin "ID") (pinfunction "ID_ID") (pintype "bidirectional"))
    )
    (net (code "69") (name "unconnected-(U4-CBUS0-Pad18)") (class "Default")
      (node (ref "U4") (pin "18") (pinfunction "CBUS0_18") (pintype "bidirectional"))
    )
    (net (code "70") (name "unconnected-(U4-CBUS1-Pad17)") (class "Default")
      (node (ref "U4") (pin "17") (pinfunction "CBUS1_17") (pintype "bidirectional"))
    )
    (net (code "71") (name "unconnected-(U4-CBUS2-Pad10)") (class "Default")
      (node (ref "U4") (pin "10") (pinfunction "CBUS2_10") (pintype "bidirectional"))
    )
    (net (code "72") (name "unconnected-(U4-CBUS3-Pad19)") (class "Default")
      (node (ref "U4") (pin "19") (pinfunction "CBUS3_19") (pintype "bidirectional"))
    )
    (net (code "73") (name "unconnected-(U4-~{CTS}-Pad9)") (class "Default")
      (node (ref "U4") (pin "9") (pinfunction "~{CTS}_9") (pintype "bidirectional"))
    )
    (net (code "74") (name "unconnected-(U4-~{DCD}-Pad8)") (class "Default")
      (node (ref "U4") (pin "8") (pinfunction "~{DCD}_8") (pintype "bidirectional"))
    )
    (net (code "75") (name "unconnected-(U4-~{DSR}-Pad7)") (class "Default")
      (node (ref "U4") (pin "7") (pinfunction "~{DSR}_7") (pintype "bidirectional"))
    )
    (net (code "76") (name "unconnected-(U4-~{RI}-Pad5)") (class "Default")
      (node (ref "U4") (pin "5") (pinfunction "~{RI}_5") (pintype "bidirectional"))
    )
    (net (code "77") (name "unconnected-(U7-BP-Pad4)") (class "Default")
      (node (ref "U7") (pin "4") (pinfunction "BP_4") (pintype "input"))
    )
  )
)
